# RelayOutput.net
KiCad netlist of a schematic drawn in Altium Designer
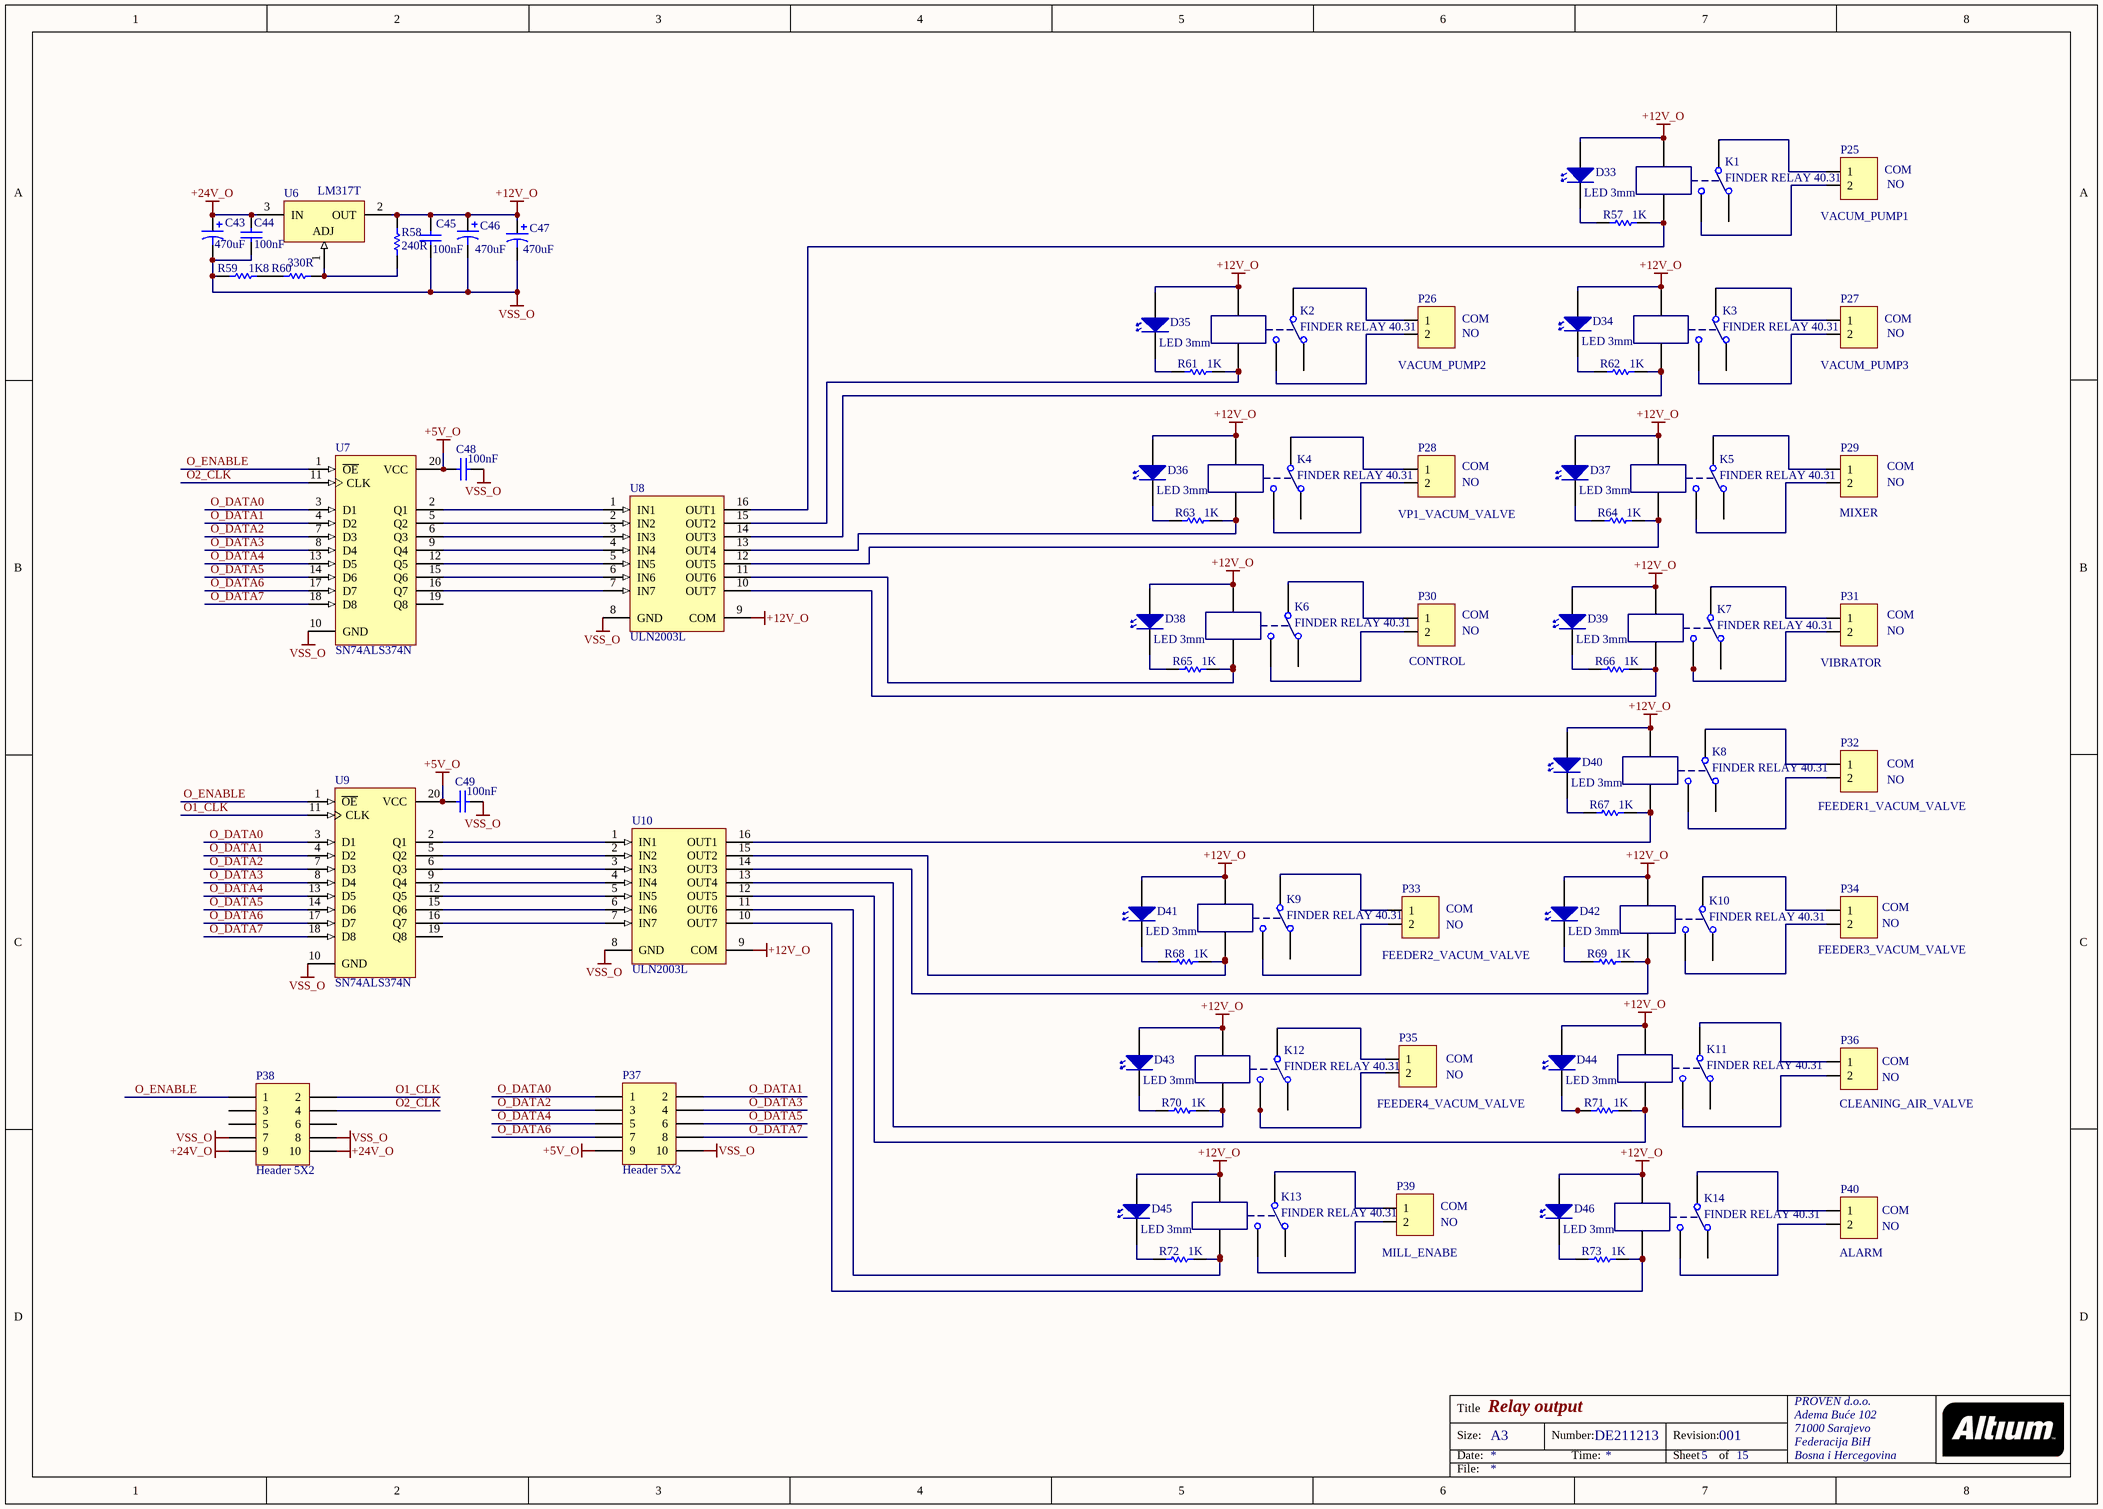
[diagram p0: RelayOutput.SchDoc]

(export (version "E")
  (design (tool "Eeschema 10.0.6"))
  (components
    (comp (ref "C43")
      (value "470uF")
      (footprint "CAPPR5-10X16")
      (description "Aluminum Electrolytic Capacitor, Radial Style with Long Leads: 470uF, 35V")
      (fields (field (name "PUBLISHER") "Altium Limited"))
      (libsource (lib "Vishay Roederstein Electrolytic Radial-Lead Capacitor") (part "EKA00DD347F00"))
    )
    (comp (ref "C44")
      (value "100nF")
      (footprint "1206")
      (description "Ceramic Chip Capacitor - Standard")
      (fields (field (name "PUBLISHER") "Altium Limited"))
      (libsource (lib "KEMET Chip Capacitor") (part "C1206"))
    )
    (comp (ref "C45")
      (value "100nF")
      (footprint "1206")
      (description "Ceramic Chip Capacitor - Standard")
      (fields (field (name "PUBLISHER") "Altium Limited"))
      (libsource (lib "KEMET Chip Capacitor") (part "C1206"))
    )
    (comp (ref "C46")
      (value "470uF")
      (footprint "CAPPR5-10X16")
      (description "Aluminum Electrolytic Capacitor, Radial Style with Long Leads: 470uF, 35V")
      (fields (field (name "PUBLISHER") "Altium Limited"))
      (libsource (lib "Vishay Roederstein Electrolytic Radial-Lead Capacitor") (part "EKA00DD347F00"))
    )
    (comp (ref "C47")
      (value "470uF")
      (footprint "CAPPR5-10X16")
      (description "Aluminum Electrolytic Capacitor, Radial Style with Long Leads: 470uF, 35V")
      (fields (field (name "PUBLISHER") "Altium Limited"))
      (libsource (lib "Vishay Roederstein Electrolytic Radial-Lead Capacitor") (part "EKA00DD347F00"))
    )
    (comp (ref "C48")
      (value "100nF")
      (footprint "1206")
      (description "Ceramic Chip Capacitor - Standard")
      (fields (field (name "PUBLISHER") "Altium Limited"))
      (libsource (lib "KEMET Chip Capacitor") (part "C1206"))
    )
    (comp (ref "C49")
      (value "100nF")
      (footprint "1206")
      (description "Ceramic Chip Capacitor - Standard")
      (fields (field (name "PUBLISHER") "Altium Limited"))
      (libsource (lib "KEMET Chip Capacitor") (part "C1206"))
    )
    (comp (ref "D33")
      (value "LED 3mm")
      (footprint "LED 3mm")
      (libsource (lib "ProjectLibrary") (part "LED 3mm"))
    )
    (comp (ref "D34")
      (value "LED 3mm")
      (footprint "LED 3mm")
      (libsource (lib "ProjectLibrary") (part "LED 3mm"))
    )
    (comp (ref "D35")
      (value "LED 3mm")
      (footprint "LED 3mm")
      (libsource (lib "ProjectLibrary") (part "LED 3mm"))
    )
    (comp (ref "D36")
      (value "LED 3mm")
      (footprint "LED 3mm")
      (libsource (lib "ProjectLibrary") (part "LED 3mm"))
    )
    (comp (ref "D37")
      (value "LED 3mm")
      (footprint "LED 3mm")
      (libsource (lib "ProjectLibrary") (part "LED 3mm"))
    )
    (comp (ref "D38")
      (value "LED 3mm")
      (footprint "LED 3mm")
      (libsource (lib "ProjectLibrary") (part "LED 3mm"))
    )
    (comp (ref "D39")
      (value "LED 3mm")
      (footprint "LED 3mm")
      (libsource (lib "ProjectLibrary") (part "LED 3mm"))
    )
    (comp (ref "D40")
      (value "LED 3mm")
      (footprint "LED 3mm")
      (libsource (lib "ProjectLibrary") (part "LED 3mm"))
    )
    (comp (ref "D41")
      (value "LED 3mm")
      (footprint "LED 3mm")
      (libsource (lib "ProjectLibrary") (part "LED 3mm"))
    )
    (comp (ref "D42")
      (value "LED 3mm")
      (footprint "LED 3mm")
      (libsource (lib "ProjectLibrary") (part "LED 3mm"))
    )
    (comp (ref "D43")
      (value "LED 3mm")
      (footprint "LED 3mm")
      (libsource (lib "ProjectLibrary") (part "LED 3mm"))
    )
    (comp (ref "D44")
      (value "LED 3mm")
      (footprint "LED 3mm")
      (libsource (lib "ProjectLibrary") (part "LED 3mm"))
    )
    (comp (ref "D45")
      (value "LED 3mm")
      (footprint "LED 3mm")
      (libsource (lib "ProjectLibrary") (part "LED 3mm"))
    )
    (comp (ref "D46")
      (value "LED 3mm")
      (footprint "LED 3mm")
      (libsource (lib "ProjectLibrary") (part "LED 3mm"))
    )
    (comp (ref "K1")
      (value "FINDER RELAY 40.31")
      (footprint "FINDER 40.31")
      (libsource (lib "") (part "FINDER RELAY 40.31_1"))
    )
    (comp (ref "K2")
      (value "FINDER RELAY 40.31")
      (footprint "FINDER 40.31")
      (libsource (lib "") (part "FINDER RELAY 40.31_1"))
    )
    (comp (ref "K3")
      (value "FINDER RELAY 40.31")
      (footprint "FINDER 40.31")
      (libsource (lib "") (part "FINDER RELAY 40.31_1"))
    )
    (comp (ref "K4")
      (value "FINDER RELAY 40.31")
      (footprint "FINDER 40.31")
      (libsource (lib "") (part "FINDER RELAY 40.31_1"))
    )
    (comp (ref "K5")
      (value "FINDER RELAY 40.31")
      (footprint "FINDER 40.31")
      (libsource (lib "") (part "FINDER RELAY 40.31_1"))
    )
    (comp (ref "K6")
      (value "FINDER RELAY 40.31")
      (footprint "FINDER 40.31")
      (libsource (lib "") (part "FINDER RELAY 40.31_1"))
    )
    (comp (ref "K7")
      (value "FINDER RELAY 40.31")
      (footprint "FINDER 40.31")
      (libsource (lib "ProjectLibrary") (part "FINDER RELAY 40.31"))
    )
    (comp (ref "K8")
      (value "FINDER RELAY 40.31")
      (footprint "FINDER 40.31")
      (libsource (lib "") (part "FINDER RELAY 40.31_1"))
    )
    (comp (ref "K9")
      (value "FINDER RELAY 40.31")
      (footprint "FINDER 40.31")
      (libsource (lib "ProjectLibrary") (part "FINDER RELAY 40.31"))
    )
    (comp (ref "K10")
      (value "FINDER RELAY 40.31")
      (footprint "FINDER 40.31")
      (libsource (lib "ProjectLibrary") (part "FINDER RELAY 40.31"))
    )
    (comp (ref "K11")
      (value "FINDER RELAY 40.31")
      (footprint "FINDER 40.31")
      (libsource (lib "") (part "FINDER RELAY 40.31_2"))
    )
    (comp (ref "K12")
      (value "FINDER RELAY 40.31")
      (footprint "FINDER 40.31")
      (libsource (lib "") (part "FINDER RELAY 40.31_2"))
    )
    (comp (ref "K13")
      (value "FINDER RELAY 40.31")
      (footprint "FINDER 40.31")
      (libsource (lib "") (part "FINDER RELAY 40.31_2"))
    )
    (comp (ref "K14")
      (value "FINDER RELAY 40.31")
      (footprint "FINDER 40.31")
      (libsource (lib "") (part "FINDER RELAY 40.31_2"))
    )
    (comp (ref "P25")
      (value "VACUM_PUMP1")
      (footprint "TERMINAL BLOK 2")
      (description "Terminal blok 2")
      (libsource (lib "") (part "Terminal blok 2 pina_1"))
    )
    (comp (ref "P26")
      (value "VACUM_PUMP2")
      (footprint "TERMINAL BLOK 2")
      (description "Terminal blok 2")
      (libsource (lib "") (part "Terminal blok 2 pina_1"))
    )
    (comp (ref "P27")
      (value "VACUM_PUMP3")
      (footprint "TERMINAL BLOK 2")
      (description "Terminal blok 2")
      (libsource (lib "") (part "Terminal blok 2 pina_1"))
    )
    (comp (ref "P28")
      (value "VP1_VACUM_VALVE")
      (footprint "TERMINAL BLOK 2")
      (description "Terminal blok 2")
      (libsource (lib "TERMINAL_CONNECOR_2") (part "Terminal blok 2 pina"))
    )
    (comp (ref "P29")
      (value "MIXER")
      (footprint "TERMINAL BLOK 2")
      (description "Terminal blok 2")
      (libsource (lib "TERMINAL_CONNECOR_2") (part "Terminal blok 2 pina"))
    )
    (comp (ref "P30")
      (value "CONTROL")
      (footprint "TERMINAL BLOK 2")
      (description "Terminal blok 2")
      (libsource (lib "TERMINAL_CONNECOR_2") (part "Terminal blok 2 pina"))
    )
    (comp (ref "P31")
      (value "VIBRATOR")
      (footprint "TERMINAL BLOK 2")
      (description "Terminal blok 2")
      (libsource (lib "TERMINAL_CONNECOR_2") (part "Terminal blok 2 pina"))
    )
    (comp (ref "P32")
      (value "FEEDER1_VACUM_VALVE")
      (footprint "TERMINAL BLOK 2")
      (description "Terminal blok 2")
      (libsource (lib "TERMINAL_CONNECOR_2") (part "Terminal blok 2 pina"))
    )
    (comp (ref "P33")
      (value "FEEDER2_VACUM_VALVE")
      (footprint "TERMINAL BLOK 2")
      (description "Terminal blok 2")
      (libsource (lib "TERMINAL_CONNECOR_2") (part "Terminal blok 2 pina"))
    )
    (comp (ref "P34")
      (value "FEEDER3_VACUM_VALVE")
      (footprint "TERMINAL BLOK 2")
      (description "Terminal blok 2")
      (libsource (lib "TERMINAL_CONNECOR_2") (part "Terminal blok 2 pina"))
    )
    (comp (ref "P35")
      (value "FEEDER4_VACUM_VALVE")
      (footprint "TERMINAL BLOK 2")
      (description "Terminal blok 2")
      (libsource (lib "TERMINAL_CONNECOR_2") (part "Terminal blok 2 pina"))
    )
    (comp (ref "P36")
      (value "CLEANING_AIR_VALVE")
      (footprint "TERMINAL BLOK 2")
      (description "Terminal blok 2")
      (libsource (lib "TERMINAL_CONNECOR_2") (part "Terminal blok 2 pina"))
    )
    (comp (ref "P37")
      (value "Header 5X2")
      (footprint "HDR2X5")
      (description "Header, 5-Pin, Dual row")
      (fields (field (name "PUBLISHER") "Altium Limited"))
      (libsource (lib "Miscellaneous Connectors") (part "Header 5X2"))
    )
    (comp (ref "P38")
      (value "Header 5X2")
      (footprint "HDR2X5")
      (description "Header, 5-Pin, Dual row")
      (fields (field (name "PUBLISHER") "Altium Limited"))
      (libsource (lib "Miscellaneous Connectors") (part "Header 5X2"))
    )
    (comp (ref "P39")
      (value "MILL_ENABE")
      (footprint "TERMINAL BLOK 2")
      (description "Terminal blok 2")
      (libsource (lib "TERMINAL_CONNECOR_2") (part "Terminal blok 2 pina"))
    )
    (comp (ref "P40")
      (value "ALARM")
      (footprint "TERMINAL BLOK 2")
      (description "Terminal blok 2")
      (libsource (lib "TERMINAL_CONNECOR_2") (part "Terminal blok 2 pina"))
    )
    (comp (ref "R57")
      (value "1K")
      (footprint "ERA-0805")
      (fields (field (name "PUBLISHER") "Altium Limited"))
      (libsource (lib "Panasonic Resistor") (part "ERAS"))
    )
    (comp (ref "R58")
      (value "240R")
      (footprint "ERA-0805")
      (fields (field (name "PUBLISHER") "Altium Limited"))
      (libsource (lib "Panasonic Resistor") (part "ERAS"))
    )
    (comp (ref "R59")
      (value "1K8")
      (footprint "ERA-0805")
      (fields (field (name "PUBLISHER") "Altium Limited"))
      (libsource (lib "Panasonic Resistor") (part "ERAS"))
    )
    (comp (ref "R60")
      (value "330R")
      (footprint "ERA-0805")
      (fields (field (name "PUBLISHER") "Altium Limited"))
      (libsource (lib "Panasonic Resistor") (part "ERAS"))
    )
    (comp (ref "R61")
      (value "1K")
      (footprint "ERA-0805")
      (fields (field (name "PUBLISHER") "Altium Limited"))
      (libsource (lib "Panasonic Resistor") (part "ERAS"))
    )
    (comp (ref "R62")
      (value "1K")
      (footprint "ERA-0805")
      (fields (field (name "PUBLISHER") "Altium Limited"))
      (libsource (lib "Panasonic Resistor") (part "ERAS"))
    )
    (comp (ref "R63")
      (value "1K")
      (footprint "ERA-0805")
      (fields (field (name "PUBLISHER") "Altium Limited"))
      (libsource (lib "Panasonic Resistor") (part "ERAS"))
    )
    (comp (ref "R64")
      (value "1K")
      (footprint "ERA-0805")
      (fields (field (name "PUBLISHER") "Altium Limited"))
      (libsource (lib "Panasonic Resistor") (part "ERAS"))
    )
    (comp (ref "R65")
      (value "1K")
      (footprint "ERA-0805")
      (fields (field (name "PUBLISHER") "Altium Limited"))
      (libsource (lib "Panasonic Resistor") (part "ERAS"))
    )
    (comp (ref "R66")
      (value "1K")
      (footprint "ERA-0805")
      (fields (field (name "PUBLISHER") "Altium Limited"))
      (libsource (lib "Panasonic Resistor") (part "ERAS"))
    )
    (comp (ref "R67")
      (value "1K")
      (footprint "ERA-0805")
      (fields (field (name "PUBLISHER") "Altium Limited"))
      (libsource (lib "Panasonic Resistor") (part "ERAS"))
    )
    (comp (ref "R68")
      (value "1K")
      (footprint "ERA-0805")
      (fields (field (name "PUBLISHER") "Altium Limited"))
      (libsource (lib "Panasonic Resistor") (part "ERAS"))
    )
    (comp (ref "R69")
      (value "1K")
      (footprint "ERA-0805")
      (fields (field (name "PUBLISHER") "Altium Limited"))
      (libsource (lib "Panasonic Resistor") (part "ERAS"))
    )
    (comp (ref "R70")
      (value "1K")
      (footprint "ERA-0805")
      (fields (field (name "PUBLISHER") "Altium Limited"))
      (libsource (lib "Panasonic Resistor") (part "ERAS"))
    )
    (comp (ref "R71")
      (value "1K")
      (footprint "ERA-0805")
      (fields (field (name "PUBLISHER") "Altium Limited"))
      (libsource (lib "Panasonic Resistor") (part "ERAS"))
    )
    (comp (ref "R72")
      (value "1K")
      (footprint "ERA-0805")
      (fields (field (name "PUBLISHER") "Altium Limited"))
      (libsource (lib "Panasonic Resistor") (part "ERAS"))
    )
    (comp (ref "R73")
      (value "1K")
      (footprint "ERA-0805")
      (fields (field (name "PUBLISHER") "Altium Limited"))
      (libsource (lib "Panasonic Resistor") (part "ERAS"))
    )
    (comp (ref "U6")
      (value "LM317T")
      (footprint "221A-04")
      (description "3-Terminal Adjustable Positive Voltage Regulator")
      (fields (field (name "PUBLISHER") "Altium Limited"))
      (libsource (lib "Motorola Power Mgt Voltage Regulator") (part "LM317T"))
    )
    (comp (ref "U7")
      (value "SN74ALS374N")
      (footprint "N020D")
      (description "Octal D-Type Edge-Triggered Flip-Flop with 3-State Outputs")
      (fields (field (name "PUBLISHER") "Altium Limited"))
      (libsource (lib "TI Logic Flip-Flop") (part "SN74ALS374N"))
    )
    (comp (ref "U8")
      (value "ULN2003L")
      (footprint "L16_N")
      (description "High-Voltage, High-Current Darlington Array")
      (fields (field (name "PUBLISHER") "Altium Limited"))
      (libsource (lib "Allegro Interface Darlington Driver") (part "ULN2003L"))
    )
    (comp (ref "U9")
      (value "SN74ALS374N")
      (footprint "N020D")
      (description "Octal D-Type Edge-Triggered Flip-Flop with 3-State Outputs")
      (fields (field (name "PUBLISHER") "Altium Limited"))
      (libsource (lib "TI Logic Flip-Flop") (part "SN74ALS374N"))
    )
    (comp (ref "U10")
      (value "ULN2003L")
      (footprint "L16_N")
      (description "High-Voltage, High-Current Darlington Array")
      (fields (field (name "PUBLISHER") "Altium Limited"))
      (libsource (lib "Allegro Interface Darlington Driver") (part "ULN2003L"))
    )
  )
  (nets
    (net (code "1") (name "+5V_O") (class "Default")
      (node (ref "C48") (pin "1") (pinfunction "1_1") (pintype "passive"))
      (node (ref "C49") (pin "1") (pinfunction "1_1") (pintype "passive"))
      (node (ref "P37") (pin "9") (pinfunction "9_9") (pintype "passive"))
      (node (ref "U7") (pin "20") (pinfunction "VCC_20") (pintype "power_in"))
      (node (ref "U9") (pin "20") (pinfunction "VCC_20") (pintype "power_in"))
    )
    (net (code "2") (name "+12V_O") (class "Default")
      (node (ref "C45") (pin "2") (pinfunction "2_2") (pintype "passive"))
      (node (ref "C46") (pin "1") (pinfunction "1_1") (pintype "passive"))
      (node (ref "C47") (pin "1") (pinfunction "1_1") (pintype "passive"))
      (node (ref "D33") (pin "2") (pinfunction "2_2") (pintype "passive"))
      (node (ref "D34") (pin "2") (pinfunction "2_2") (pintype "passive"))
      (node (ref "D35") (pin "2") (pinfunction "2_2") (pintype "passive"))
      (node (ref "D36") (pin "2") (pinfunction "2_2") (pintype "passive"))
      (node (ref "D37") (pin "2") (pinfunction "2_2") (pintype "passive"))
      (node (ref "D38") (pin "2") (pinfunction "2_2") (pintype "passive"))
      (node (ref "D39") (pin "2") (pinfunction "2_2") (pintype "passive"))
      (node (ref "D40") (pin "2") (pinfunction "2_2") (pintype "passive"))
      (node (ref "D41") (pin "2") (pinfunction "2_2") (pintype "passive"))
      (node (ref "D42") (pin "2") (pinfunction "2_2") (pintype "passive"))
      (node (ref "D43") (pin "2") (pinfunction "2_2") (pintype "passive"))
      (node (ref "D44") (pin "2") (pinfunction "2_2") (pintype "passive"))
      (node (ref "D45") (pin "2") (pinfunction "2_2") (pintype "passive"))
      (node (ref "D46") (pin "2") (pinfunction "2_2") (pintype "passive"))
      (node (ref "K1") (pin "1") (pinfunction "1_1") (pintype "passive"))
      (node (ref "K10") (pin "1") (pinfunction "1_1") (pintype "passive"))
      (node (ref "K11") (pin "1") (pinfunction "1_1") (pintype "passive"))
      (node (ref "K12") (pin "1") (pinfunction "1_1") (pintype "passive"))
      (node (ref "K13") (pin "1") (pinfunction "1_1") (pintype "passive"))
      (node (ref "K14") (pin "1") (pinfunction "1_1") (pintype "passive"))
      (node (ref "K2") (pin "1") (pinfunction "1_1") (pintype "passive"))
      (node (ref "K3") (pin "1") (pinfunction "1_1") (pintype "passive"))
      (node (ref "K4") (pin "1") (pinfunction "1_1") (pintype "passive"))
      (node (ref "K5") (pin "1") (pinfunction "1_1") (pintype "passive"))
      (node (ref "K6") (pin "1") (pinfunction "1_1") (pintype "passive"))
      (node (ref "K7") (pin "1") (pinfunction "1_1") (pintype "passive"))
      (node (ref "K8") (pin "1") (pinfunction "1_1") (pintype "passive"))
      (node (ref "K9") (pin "1") (pinfunction "1_1") (pintype "passive"))
      (node (ref "R58") (pin "2") (pinfunction "2_2") (pintype "passive"))
      (node (ref "U10") (pin "9") (pinfunction "COM_9") (pintype "passive"))
      (node (ref "U6") (pin "2") (pinfunction "OUT_2") (pintype "power_in"))
      (node (ref "U8") (pin "9") (pinfunction "COM_9") (pintype "passive"))
    )
    (net (code "3") (name "+24V_O") (class "Default")
      (node (ref "C43") (pin "1") (pinfunction "1_1") (pintype "passive"))
      (node (ref "C44") (pin "2") (pinfunction "2_2") (pintype "passive"))
      (node (ref "P38") (pin "10") (pinfunction "10_10") (pintype "passive"))
      (node (ref "P38") (pin "9") (pinfunction "9_9") (pintype "passive"))
      (node (ref "U6") (pin "3") (pinfunction "IN_3") (pintype "power_in"))
    )
    (net (code "4") (name "/O1_CLK") (class "Default")
      (node (ref "P38") (pin "2") (pinfunction "2_2") (pintype "passive"))
      (node (ref "U9") (pin "11") (pinfunction "CLK_11") (pintype "input"))
    )
    (net (code "5") (name "/O2_CLK") (class "Default")
      (node (ref "P38") (pin "4") (pinfunction "4_4") (pintype "passive"))
      (node (ref "U7") (pin "11") (pinfunction "CLK_11") (pintype "input"))
    )
    (net (code "6") (name "/O_DATA0") (class "Default")
      (node (ref "P37") (pin "1") (pinfunction "1_1") (pintype "passive"))
      (node (ref "U7") (pin "3") (pinfunction "D1_3") (pintype "input"))
      (node (ref "U9") (pin "3") (pinfunction "D1_3") (pintype "input"))
    )
    (net (code "7") (name "/O_DATA1") (class "Default")
      (node (ref "P37") (pin "2") (pinfunction "2_2") (pintype "passive"))
      (node (ref "U7") (pin "4") (pinfunction "D2_4") (pintype "input"))
      (node (ref "U9") (pin "4") (pinfunction "D2_4") (pintype "input"))
    )
    (net (code "8") (name "/O_DATA2") (class "Default")
      (node (ref "P37") (pin "3") (pinfunction "3_3") (pintype "passive"))
      (node (ref "U7") (pin "7") (pinfunction "D3_7") (pintype "input"))
      (node (ref "U9") (pin "7") (pinfunction "D3_7") (pintype "input"))
    )
    (net (code "9") (name "/O_DATA3") (class "Default")
      (node (ref "P37") (pin "4") (pinfunction "4_4") (pintype "passive"))
      (node (ref "U7") (pin "8") (pinfunction "D4_8") (pintype "input"))
      (node (ref "U9") (pin "8") (pinfunction "D4_8") (pintype "input"))
    )
    (net (code "10") (name "/O_DATA4") (class "Default")
      (node (ref "P37") (pin "5") (pinfunction "5_5") (pintype "passive"))
      (node (ref "U7") (pin "13") (pinfunction "D5_13") (pintype "input"))
      (node (ref "U9") (pin "13") (pinfunction "D5_13") (pintype "input"))
    )
    (net (code "11") (name "/O_DATA5") (class "Default")
      (node (ref "P37") (pin "6") (pinfunction "6_6") (pintype "passive"))
      (node (ref "U7") (pin "14") (pinfunction "D6_14") (pintype "input"))
      (node (ref "U9") (pin "14") (pinfunction "D6_14") (pintype "input"))
    )
    (net (code "12") (name "/O_DATA6") (class "Default")
      (node (ref "P37") (pin "7") (pinfunction "7_7") (pintype "passive"))
      (node (ref "U7") (pin "17") (pinfunction "D7_17") (pintype "input"))
      (node (ref "U9") (pin "17") (pinfunction "D7_17") (pintype "input"))
    )
    (net (code "13") (name "/O_DATA7") (class "Default")
      (node (ref "P37") (pin "8") (pinfunction "8_8") (pintype "passive"))
      (node (ref "U7") (pin "18") (pinfunction "D8_18") (pintype "input"))
      (node (ref "U9") (pin "18") (pinfunction "D8_18") (pintype "input"))
    )
    (net (code "14") (name "/O_ENABLE") (class "Default")
      (node (ref "P38") (pin "1") (pinfunction "1_1") (pintype "passive"))
      (node (ref "U7") (pin "1") (pinfunction "~{OE}_1") (pintype "input"))
      (node (ref "U9") (pin "1") (pinfunction "~{OE}_1") (pintype "input"))
    )
    (net (code "15") (name "Net-(D33-Pad1)") (class "Default")
      (node (ref "D33") (pin "1") (pinfunction "1_1") (pintype "passive"))
      (node (ref "R57") (pin "1") (pinfunction "1_1") (pintype "passive"))
    )
    (net (code "16") (name "Net-(D34-Pad1)") (class "Default")
      (node (ref "D34") (pin "1") (pinfunction "1_1") (pintype "passive"))
      (node (ref "R62") (pin "1") (pinfunction "1_1") (pintype "passive"))
    )
    (net (code "17") (name "Net-(D35-Pad1)") (class "Default")
      (node (ref "D35") (pin "1") (pinfunction "1_1") (pintype "passive"))
      (node (ref "R61") (pin "1") (pinfunction "1_1") (pintype "passive"))
    )
    (net (code "18") (name "Net-(D36-Pad1)") (class "Default")
      (node (ref "D36") (pin "1") (pinfunction "1_1") (pintype "passive"))
      (node (ref "R63") (pin "1") (pinfunction "1_1") (pintype "passive"))
    )
    (net (code "19") (name "Net-(D37-Pad1)") (class "Default")
      (node (ref "D37") (pin "1") (pinfunction "1_1") (pintype "passive"))
      (node (ref "R64") (pin "1") (pinfunction "1_1") (pintype "passive"))
    )
    (net (code "20") (name "Net-(D38-Pad1)") (class "Default")
      (node (ref "D38") (pin "1") (pinfunction "1_1") (pintype "passive"))
      (node (ref "R65") (pin "1") (pinfunction "1_1") (pintype "passive"))
    )
    (net (code "21") (name "Net-(D39-Pad1)") (class "Default")
      (node (ref "D39") (pin "1") (pinfunction "1_1") (pintype "passive"))
      (node (ref "R66") (pin "1") (pinfunction "1_1") (pintype "passive"))
    )
    (net (code "22") (name "Net-(D40-Pad1)") (class "Default")
      (node (ref "D40") (pin "1") (pinfunction "1_1") (pintype "passive"))
      (node (ref "R67") (pin "1") (pinfunction "1_1") (pintype "passive"))
    )
    (net (code "23") (name "Net-(D41-Pad1)") (class "Default")
      (node (ref "D41") (pin "1") (pinfunction "1_1") (pintype "passive"))
      (node (ref "R68") (pin "1") (pinfunction "1_1") (pintype "passive"))
    )
    (net (code "24") (name "Net-(D42-Pad1)") (class "Default")
      (node (ref "D42") (pin "1") (pinfunction "1_1") (pintype "passive"))
      (node (ref "R69") (pin "1") (pinfunction "1_1") (pintype "passive"))
    )
    (net (code "25") (name "Net-(D43-Pad1)") (class "Default")
      (node (ref "D43") (pin "1") (pinfunction "1_1") (pintype "passive"))
      (node (ref "R70") (pin "1") (pinfunction "1_1") (pintype "passive"))
    )
    (net (code "26") (name "Net-(D44-Pad1)") (class "Default")
      (node (ref "D44") (pin "1") (pinfunction "1_1") (pintype "passive"))
      (node (ref "R71") (pin "1") (pinfunction "1_1") (pintype "passive"))
    )
    (net (code "27") (name "Net-(D45-Pad1)") (class "Default")
      (node (ref "D45") (pin "1") (pinfunction "1_1") (pintype "passive"))
      (node (ref "R72") (pin "1") (pinfunction "1_1") (pintype "passive"))
    )
    (net (code "28") (name "Net-(D46-Pad1)") (class "Default")
      (node (ref "D46") (pin "1") (pinfunction "1_1") (pintype "passive"))
      (node (ref "R73") (pin "1") (pinfunction "1_1") (pintype "passive"))
    )
    (net (code "29") (name "Net-(K1-Pad3)") (class "Default")
      (node (ref "K1") (pin "3") (pinfunction "3_3") (pintype "passive"))
      (node (ref "P25") (pin "1") (pinfunction "1_1") (pintype "passive"))
    )
    (net (code "30") (name "Net-(K1-Pad4)") (class "Default")
      (node (ref "K1") (pin "4") (pinfunction "4_4") (pintype "passive"))
      (node (ref "P25") (pin "2") (pinfunction "2_2") (pintype "passive"))
    )
    (net (code "31") (name "Net-(K2-Pad3)") (class "Default")
      (node (ref "K2") (pin "3") (pinfunction "3_3") (pintype "passive"))
      (node (ref "P26") (pin "1") (pinfunction "1_1") (pintype "passive"))
    )
    (net (code "32") (name "Net-(K2-Pad4)") (class "Default")
      (node (ref "K2") (pin "4") (pinfunction "4_4") (pintype "passive"))
      (node (ref "P26") (pin "2") (pinfunction "2_2") (pintype "passive"))
    )
    (net (code "33") (name "Net-(K3-Pad3)") (class "Default")
      (node (ref "K3") (pin "3") (pinfunction "3_3") (pintype "passive"))
      (node (ref "P27") (pin "1") (pinfunction "1_1") (pintype "passive"))
    )
    (net (code "34") (name "Net-(K3-Pad4)") (class "Default")
      (node (ref "K3") (pin "4") (pinfunction "4_4") (pintype "passive"))
      (node (ref "P27") (pin "2") (pinfunction "2_2") (pintype "passive"))
    )
    (net (code "35") (name "Net-(K4-Pad3)") (class "Default")
      (node (ref "K4") (pin "3") (pinfunction "3_3") (pintype "passive"))
      (node (ref "P28") (pin "1") (pinfunction "1_1") (pintype "passive"))
    )
    (net (code "36") (name "Net-(K4-Pad4)") (class "Default")
      (node (ref "K4") (pin "4") (pinfunction "4_4") (pintype "passive"))
      (node (ref "P28") (pin "2") (pinfunction "2_2") (pintype "passive"))
    )
    (net (code "37") (name "Net-(K5-Pad3)") (class "Default")
      (node (ref "K5") (pin "3") (pinfunction "3_3") (pintype "passive"))
      (node (ref "P29") (pin "1") (pinfunction "1_1") (pintype "passive"))
    )
    (net (code "38") (name "Net-(K5-Pad4)") (class "Default")
      (node (ref "K5") (pin "4") (pinfunction "4_4") (pintype "passive"))
      (node (ref "P29") (pin "2") (pinfunction "2_2") (pintype "passive"))
    )
    (net (code "39") (name "Net-(K6-Pad3)") (class "Default")
      (node (ref "K6") (pin "3") (pinfunction "3_3") (pintype "passive"))
      (node (ref "P30") (pin "1") (pinfunction "1_1") (pintype "passive"))
    )
    (net (code "40") (name "Net-(K6-Pad4)") (class "Default")
      (node (ref "K6") (pin "4") (pinfunction "4_4") (pintype "passive"))
      (node (ref "P30") (pin "2") (pinfunction "2_2") (pintype "passive"))
    )
    (net (code "41") (name "Net-(K7-Pad3)") (class "Default")
      (node (ref "K7") (pin "3") (pinfunction "3_3") (pintype "passive"))
      (node (ref "P31") (pin "1") (pinfunction "1_1") (pintype "passive"))
    )
    (net (code "42") (name "Net-(K7-Pad4)") (class "Default")
      (node (ref "K7") (pin "4") (pinfunction "4_4") (pintype "passive"))
      (node (ref "P31") (pin "2") (pinfunction "2_2") (pintype "passive"))
    )
    (net (code "43") (name "Net-(K8-Pad3)") (class "Default")
      (node (ref "K8") (pin "3") (pinfunction "3_3") (pintype "passive"))
      (node (ref "P32") (pin "1") (pinfunction "1_1") (pintype "passive"))
    )
    (net (code "44") (name "Net-(K8-Pad4)") (class "Default")
      (node (ref "K8") (pin "4") (pinfunction "4_4") (pintype "passive"))
      (node (ref "P32") (pin "2") (pinfunction "2_2") (pintype "passive"))
    )
    (net (code "45") (name "Net-(K9-Pad3)") (class "Default")
      (node (ref "K9") (pin "3") (pinfunction "3_3") (pintype "passive"))
      (node (ref "P33") (pin "1") (pinfunction "1_1") (pintype "passive"))
    )
    (net (code "46") (name "Net-(K9-Pad4)") (class "Default")
      (node (ref "K9") (pin "4") (pinfunction "4_4") (pintype "passive"))
      (node (ref "P33") (pin "2") (pinfunction "2_2") (pintype "passive"))
    )
    (net (code "47") (name "Net-(K10-Pad3)") (class "Default")
      (node (ref "K10") (pin "3") (pinfunction "3_3") (pintype "passive"))
      (node (ref "P34") (pin "1") (pinfunction "1_1") (pintype "passive"))
    )
    (net (code "48") (name "Net-(K10-Pad4)") (class "Default")
      (node (ref "K10") (pin "4") (pinfunction "4_4") (pintype "passive"))
      (node (ref "P34") (pin "2") (pinfunction "2_2") (pintype "passive"))
    )
    (net (code "49") (name "Net-(K11-Pad3)") (class "Default")
      (node (ref "K11") (pin "3") (pinfunction "3_3") (pintype "passive"))
      (node (ref "P36") (pin "1") (pinfunction "1_1") (pintype "passive"))
    )
    (net (code "50") (name "Net-(K11-Pad4)") (class "Default")
      (node (ref "K11") (pin "4") (pinfunction "4_4") (pintype "passive"))
      (node (ref "P36") (pin "2") (pinfunction "2_2") (pintype "passive"))
    )
    (net (code "51") (name "Net-(K12-Pad3)") (class "Default")
      (node (ref "K12") (pin "3") (pinfunction "3_3") (pintype "passive"))
      (node (ref "P35") (pin "1") (pinfunction "1_1") (pintype "passive"))
    )
    (net (code "52") (name "Net-(K12-Pad4)") (class "Default")
      (node (ref "K12") (pin "4") (pinfunction "4_4") (pintype "passive"))
      (node (ref "P35") (pin "2") (pinfunction "2_2") (pintype "passive"))
    )
    (net (code "53") (name "Net-(K13-Pad3)") (class "Default")
      (node (ref "K13") (pin "3") (pinfunction "3_3") (pintype "passive"))
      (node (ref "P39") (pin "1") (pinfunction "1_1") (pintype "passive"))
    )
    (net (code "54") (name "Net-(K13-Pad4)") (class "Default")
      (node (ref "K13") (pin "4") (pinfunction "4_4") (pintype "passive"))
      (node (ref "P39") (pin "2") (pinfunction "2_2") (pintype "passive"))
    )
    (net (code "55") (name "Net-(K14-Pad3)") (class "Default")
      (node (ref "K14") (pin "3") (pinfunction "3_3") (pintype "passive"))
      (node (ref "P40") (pin "1") (pinfunction "1_1") (pintype "passive"))
    )
    (net (code "56") (name "Net-(K14-Pad4)") (class "Default")
      (node (ref "K14") (pin "4") (pinfunction "4_4") (pintype "passive"))
      (node (ref "P40") (pin "2") (pinfunction "2_2") (pintype "passive"))
    )
    (net (code "57") (name "Net-(R59-Pad1)") (class "Default")
      (node (ref "R59") (pin "1") (pinfunction "1_1") (pintype "passive"))
      (node (ref "R60") (pin "2") (pinfunction "2_2") (pintype "passive"))
    )
    (net (code "58") (name "Net-(U6-ADJ)") (class "Default")
      (node (ref "R58") (pin "1") (pinfunction "1_1") (pintype "passive"))
      (node (ref "R60") (pin "1") (pinfunction "1_1") (pintype "passive"))
      (node (ref "U6") (pin "1") (pinfunction "ADJ_1") (pintype "input"))
    )
    (net (code "59") (name "Net-(U7-Q1)") (class "Default")
      (node (ref "U7") (pin "2") (pinfunction "Q1_2") (pintype "tri_state"))
      (node (ref "U8") (pin "1") (pinfunction "IN1_1") (pintype "input"))
    )
    (net (code "60") (name "Net-(U7-Q2)") (class "Default")
      (node (ref "U7") (pin "5") (pinfunction "Q2_5") (pintype "tri_state"))
      (node (ref "U8") (pin "2") (pinfunction "IN2_2") (pintype "input"))
    )
    (net (code "61") (name "Net-(U7-Q3)") (class "Default")
      (node (ref "U7") (pin "6") (pinfunction "Q3_6") (pintype "tri_state"))
      (node (ref "U8") (pin "3") (pinfunction "IN3_3") (pintype "input"))
    )
    (net (code "62") (name "Net-(U7-Q4)") (class "Default")
      (node (ref "U7") (pin "9") (pinfunction "Q4_9") (pintype "tri_state"))
      (node (ref "U8") (pin "4") (pinfunction "IN4_4") (pintype "input"))
    )
    (net (code "63") (name "Net-(U7-Q5)") (class "Default")
      (node (ref "U7") (pin "12") (pinfunction "Q5_12") (pintype "tri_state"))
      (node (ref "U8") (pin "5") (pinfunction "IN5_5") (pintype "input"))
    )
    (net (code "64") (name "Net-(U7-Q6)") (class "Default")
      (node (ref "U7") (pin "15") (pinfunction "Q6_15") (pintype "tri_state"))
      (node (ref "U8") (pin "6") (pinfunction "IN6_6") (pintype "input"))
    )
    (net (code "65") (name "Net-(U7-Q7)") (class "Default")
      (node (ref "U7") (pin "16") (pinfunction "Q7_16") (pintype "tri_state"))
      (node (ref "U8") (pin "7") (pinfunction "IN7_7") (pintype "input"))
    )
    (net (code "66") (name "Net-(U8-OUT1)") (class "Default")
      (node (ref "K1") (pin "2") (pinfunction "2_2") (pintype "passive"))
      (node (ref "R57") (pin "2") (pinfunction "2_2") (pintype "passive"))
      (node (ref "U8") (pin "16") (pinfunction "OUT1_16") (pintype "open_collector"))
    )
    (net (code "67") (name "Net-(U8-OUT2)") (class "Default")
      (node (ref "K2") (pin "2") (pinfunction "2_2") (pintype "passive"))
      (node (ref "R61") (pin "2") (pinfunction "2_2") (pintype "passive"))
      (node (ref "U8") (pin "15") (pinfunction "OUT2_15") (pintype "open_collector"))
    )
    (net (code "68") (name "Net-(U8-OUT3)") (class "Default")
      (node (ref "K3") (pin "2") (pinfunction "2_2") (pintype "passive"))
      (node (ref "R62") (pin "2") (pinfunction "2_2") (pintype "passive"))
      (node (ref "U8") (pin "14") (pinfunction "OUT3_14") (pintype "open_collector"))
    )
    (net (code "69") (name "Net-(U8-OUT4)") (class "Default")
      (node (ref "K4") (pin "2") (pinfunction "2_2") (pintype "passive"))
      (node (ref "R63") (pin "2") (pinfunction "2_2") (pintype "passive"))
      (node (ref "U8") (pin "13") (pinfunction "OUT4_13") (pintype "open_collector"))
    )
    (net (code "70") (name "Net-(U8-OUT5)") (class "Default")
      (node (ref "K5") (pin "2") (pinfunction "2_2") (pintype "passive"))
      (node (ref "R64") (pin "2") (pinfunction "2_2") (pintype "passive"))
      (node (ref "U8") (pin "12") (pinfunction "OUT5_12") (pintype "open_collector"))
    )
    (net (code "71") (name "Net-(U8-OUT6)") (class "Default")
      (node (ref "K6") (pin "2") (pinfunction "2_2") (pintype "passive"))
      (node (ref "R65") (pin "2") (pinfunction "2_2") (pintype "passive"))
      (node (ref "U8") (pin "11") (pinfunction "OUT6_11") (pintype "open_collector"))
    )
    (net (code "72") (name "Net-(U8-OUT7)") (class "Default")
      (node (ref "K7") (pin "2") (pinfunction "2_2") (pintype "passive"))
      (node (ref "R66") (pin "2") (pinfunction "2_2") (pintype "passive"))
      (node (ref "U8") (pin "10") (pinfunction "OUT7_10") (pintype "open_collector"))
    )
    (net (code "73") (name "Net-(U10-IN1)") (class "Default")
      (node (ref "U10") (pin "1") (pinfunction "IN1_1") (pintype "input"))
      (node (ref "U9") (pin "2") (pinfunction "Q1_2") (pintype "tri_state"))
    )
    (net (code "74") (name "Net-(U10-IN2)") (class "Default")
      (node (ref "U10") (pin "2") (pinfunction "IN2_2") (pintype "input"))
      (node (ref "U9") (pin "5") (pinfunction "Q2_5") (pintype "tri_state"))
    )
    (net (code "75") (name "Net-(U10-IN3)") (class "Default")
      (node (ref "U10") (pin "3") (pinfunction "IN3_3") (pintype "input"))
      (node (ref "U9") (pin "6") (pinfunction "Q3_6") (pintype "tri_state"))
    )
    (net (code "76") (name "Net-(U10-IN4)") (class "Default")
      (node (ref "U10") (pin "4") (pinfunction "IN4_4") (pintype "input"))
      (node (ref "U9") (pin "9") (pinfunction "Q4_9") (pintype "tri_state"))
    )
    (net (code "77") (name "Net-(U10-IN5)") (class "Default")
      (node (ref "U10") (pin "5") (pinfunction "IN5_5") (pintype "input"))
      (node (ref "U9") (pin "12") (pinfunction "Q5_12") (pintype "tri_state"))
    )
    (net (code "78") (name "Net-(U10-IN6)") (class "Default")
      (node (ref "U10") (pin "6") (pinfunction "IN6_6") (pintype "input"))
      (node (ref "U9") (pin "15") (pinfunction "Q6_15") (pintype "tri_state"))
    )
    (net (code "79") (name "Net-(U10-IN7)") (class "Default")
      (node (ref "U10") (pin "7") (pinfunction "IN7_7") (pintype "input"))
      (node (ref "U9") (pin "16") (pinfunction "Q7_16") (pintype "tri_state"))
    )
    (net (code "80") (name "Net-(U10-OUT1)") (class "Default")
      (node (ref "K8") (pin "2") (pinfunction "2_2") (pintype "passive"))
      (node (ref "R67") (pin "2") (pinfunction "2_2") (pintype "passive"))
      (node (ref "U10") (pin "16") (pinfunction "OUT1_16") (pintype "open_collector"))
    )
    (net (code "81") (name "Net-(U10-OUT2)") (class "Default")
      (node (ref "K9") (pin "2") (pinfunction "2_2") (pintype "passive"))
      (node (ref "R68") (pin "2") (pinfunction "2_2") (pintype "passive"))
      (node (ref "U10") (pin "15") (pinfunction "OUT2_15") (pintype "open_collector"))
    )
    (net (code "82") (name "Net-(U10-OUT3)") (class "Default")
      (node (ref "K10") (pin "2") (pinfunction "2_2") (pintype "passive"))
      (node (ref "R69") (pin "2") (pinfunction "2_2") (pintype "passive"))
      (node (ref "U10") (pin "14") (pinfunction "OUT3_14") (pintype "open_collector"))
    )
    (net (code "83") (name "Net-(U10-OUT4)") (class "Default")
      (node (ref "K12") (pin "2") (pinfunction "2_2") (pintype "passive"))
      (node (ref "R70") (pin "2") (pinfunction "2_2") (pintype "passive"))
      (node (ref "U10") (pin "13") (pinfunction "OUT4_13") (pintype "open_collector"))
    )
    (net (code "84") (name "Net-(U10-OUT5)") (class "Default")
      (node (ref "K11") (pin "2") (pinfunction "2_2") (pintype "passive"))
      (node (ref "R71") (pin "2") (pinfunction "2_2") (pintype "passive"))
      (node (ref "U10") (pin "12") (pinfunction "OUT5_12") (pintype "open_collector"))
    )
    (net (code "85") (name "Net-(U10-OUT6)") (class "Default")
      (node (ref "K13") (pin "2") (pinfunction "2_2") (pintype "passive"))
      (node (ref "R72") (pin "2") (pinfunction "2_2") (pintype "passive"))
      (node (ref "U10") (pin "11") (pinfunction "OUT6_11") (pintype "open_collector"))
    )
    (net (code "86") (name "Net-(U10-OUT7)") (class "Default")
      (node (ref "K14") (pin "2") (pinfunction "2_2") (pintype "passive"))
      (node (ref "R73") (pin "2") (pinfunction "2_2") (pintype "passive"))
      (node (ref "U10") (pin "10") (pinfunction "OUT7_10") (pintype "open_collector"))
    )
    (net (code "87") (name "VSS_O") (class "Default")
      (node (ref "C43") (pin "2") (pinfunction "2_2") (pintype "passive"))
      (node (ref "C44") (pin "1") (pinfunction "1_1") (pintype "passive"))
      (node (ref "C45") (pin "1") (pinfunction "1_1") (pintype "passive"))
      (node (ref "C46") (pin "2") (pinfunction "2_2") (pintype "passive"))
      (node (ref "C47") (pin "2") (pinfunction "2_2") (pintype "passive"))
      (node (ref "C48") (pin "2") (pinfunction "2_2") (pintype "passive"))
      (node (ref "C49") (pin "2") (pinfunction "2_2") (pintype "passive"))
      (node (ref "P37") (pin "10") (pinfunction "10_10") (pintype "passive"))
      (node (ref "P38") (pin "7") (pinfunction "7_7") (pintype "passive"))
      (node (ref "P38") (pin "8") (pinfunction "8_8") (pintype "passive"))
      (node (ref "R59") (pin "2") (pinfunction "2_2") (pintype "passive"))
      (node (ref "U10") (pin "8") (pinfunction "GND_8") (pintype "power_in"))
      (node (ref "U7") (pin "10") (pinfunction "GND_10") (pintype "power_in"))
      (node (ref "U8") (pin "8") (pinfunction "GND_8") (pintype "power_in"))
      (node (ref "U9") (pin "10") (pinfunction "GND_10") (pintype "power_in"))
    )
    (net (code "88") (name "unconnected-(K1-Pad5)") (class "Default")
      (node (ref "K1") (pin "5") (pinfunction "5_5") (pintype "passive"))
    )
    (net (code "89") (name "unconnected-(K2-Pad5)") (class "Default")
      (node (ref "K2") (pin "5") (pinfunction "5_5") (pintype "passive"))
    )
    (net (code "90") (name "unconnected-(K3-Pad5)") (class "Default")
      (node (ref "K3") (pin "5") (pinfunction "5_5") (pintype "passive"))
    )
    (net (code "91") (name "unconnected-(K4-Pad5)") (class "Default")
      (node (ref "K4") (pin "5") (pinfunction "5_5") (pintype "passive"))
    )
    (net (code "92") (name "unconnected-(K5-Pad5)") (class "Default")
      (node (ref "K5") (pin "5") (pinfunction "5_5") (pintype "passive"))
    )
    (net (code "93") (name "unconnected-(K6-Pad5)") (class "Default")
      (node (ref "K6") (pin "5") (pinfunction "5_5") (pintype "passive"))
    )
    (net (code "94") (name "unconnected-(K7-Pad5)") (class "Default")
      (node (ref "K7") (pin "5") (pinfunction "5_5") (pintype "passive"))
    )
    (net (code "95") (name "unconnected-(K8-Pad5)") (class "Default")
      (node (ref "K8") (pin "5") (pinfunction "5_5") (pintype "passive"))
    )
    (net (code "96") (name "unconnected-(K9-Pad5)") (class "Default")
      (node (ref "K9") (pin "5") (pinfunction "5_5") (pintype "passive"))
    )
    (net (code "97") (name "unconnected-(K10-Pad5)") (class "Default")
      (node (ref "K10") (pin "5") (pinfunction "5_5") (pintype "passive"))
    )
    (net (code "98") (name "unconnected-(K11-Pad5)") (class "Default")
      (node (ref "K11") (pin "5") (pinfunction "5_5") (pintype "passive"))
    )
    (net (code "99") (name "unconnected-(K12-Pad5)") (class "Default")
      (node (ref "K12") (pin "5") (pinfunction "5_5") (pintype "passive"))
    )
    (net (code "100") (name "unconnected-(K13-Pad5)") (class "Default")
      (node (ref "K13") (pin "5") (pinfunction "5_5") (pintype "passive"))
    )
    (net (code "101") (name "unconnected-(K14-Pad5)") (class "Default")
      (node (ref "K14") (pin "5") (pinfunction "5_5") (pintype "passive"))
    )
    (net (code "102") (name "unconnected-(P38-Pad3)") (class "Default")
      (node (ref "P38") (pin "3") (pinfunction "3_3") (pintype "passive"))
    )
    (net (code "103") (name "unconnected-(P38-Pad5)") (class "Default")
      (node (ref "P38") (pin "5") (pinfunction "5_5") (pintype "passive"))
    )
    (net (code "104") (name "unconnected-(P38-Pad6)") (class "Default")
      (node (ref "P38") (pin "6") (pinfunction "6_6") (pintype "passive"))
    )
    (net (code "105") (name "unconnected-(U7-Q8-Pad19)") (class "Default")
      (node (ref "U7") (pin "19") (pinfunction "Q8_19") (pintype "tri_state"))
    )
    (net (code "106") (name "unconnected-(U9-Q8-Pad19)") (class "Default")
      (node (ref "U9") (pin "19") (pinfunction "Q8_19") (pintype "tri_state"))
    )
  )
)
